# TurboTest.net
KiCad netlist of a schematic drawn in EAGLE
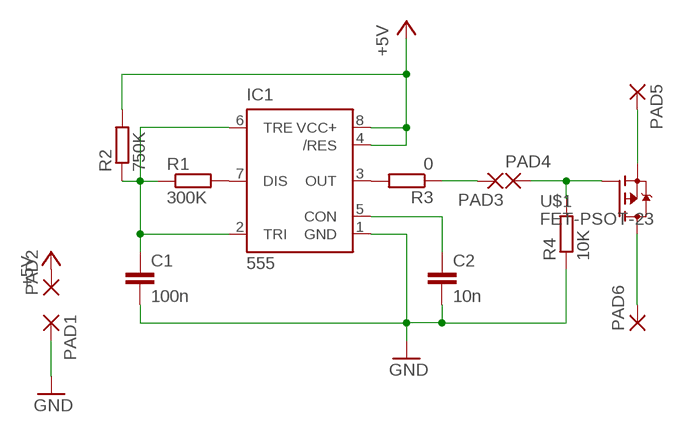
[diagram p0: schematic, sheet 1]

(export (version "E")
  (design (tool "Eeschema 10.0.6"))
  (components
    (comp (ref "C1")
      (value "100n")
      (footprint "eagle-import:CAP0805")
      (libsource (lib "eagle-import") (part "CAP_0805"))
    )
    (comp (ref "C2")
      (value "10n")
      (footprint "eagle-import:CAP0805")
      (libsource (lib "eagle-import") (part "CAP_0805"))
    )
    (comp (ref "IC1")
      (value "555")
      (footprint "eagle-import:SOIC-8")
      (libsource (lib "eagle-import") (part "IC-NE555SO8"))
    )
    (comp (ref "PAD1")
      (value "WIREPAD-SMD2")
      (footprint "eagle-import:PAD-1.27X2.54")
      (libsource (lib "eagle-import") (part "WIREPAD-SMD2"))
    )
    (comp (ref "PAD2")
      (value "WIREPAD-SMD2")
      (footprint "eagle-import:PAD-1.27X2.54")
      (libsource (lib "eagle-import") (part "WIREPAD-SMD2"))
    )
    (comp (ref "PAD3")
      (value "WIREPAD-SMD2")
      (footprint "eagle-import:PAD-1.27X2.54")
      (libsource (lib "eagle-import") (part "WIREPAD-SMD2"))
    )
    (comp (ref "PAD4")
      (value "WIREPAD-SMD2")
      (footprint "eagle-import:PAD-1.27X2.54")
      (libsource (lib "eagle-import") (part "WIREPAD-SMD2"))
    )
    (comp (ref "PAD5")
      (value "WIREPAD-SMD2")
      (footprint "eagle-import:PAD-1.27X2.54")
      (libsource (lib "eagle-import") (part "WIREPAD-SMD2"))
    )
    (comp (ref "PAD6")
      (value "WIREPAD-SMD2")
      (footprint "eagle-import:PAD-1.27X2.54")
      (libsource (lib "eagle-import") (part "WIREPAD-SMD2"))
    )
    (comp (ref "R1")
      (value "300K")
      (footprint "eagle-import:RESC2012X50")
      (libsource (lib "eagle-import") (part "R_R0805"))
    )
    (comp (ref "R2")
      (value "750K")
      (footprint "eagle-import:RESC2012X50")
      (libsource (lib "eagle-import") (part "R_R0805"))
    )
    (comp (ref "R3")
      (value "0")
      (footprint "eagle-import:RESC2012X50")
      (libsource (lib "eagle-import") (part "R_R0805"))
    )
    (comp (ref "R4")
      (value "10K")
      (footprint "eagle-import:RESC2012X50")
      (libsource (lib "eagle-import") (part "R_R0805"))
    )
    (comp (ref "U$1")
      (value "FET-PSOT-23")
      (footprint "eagle-import:SOT95P240X115-3")
      (libsource (lib "eagle-import") (part "FET-PSOT-23"))
    )
  )
  (nets
    (net (code "1") (name "+5V") (class "Default")
      (node (ref "IC1") (pin "4") (pinfunction "/RES_4") (pintype "input"))
      (node (ref "IC1") (pin "8") (pinfunction "VCC+_8") (pintype "power_in"))
      (node (ref "PAD2") (pin "P$1") (pinfunction "P_P$1") (pintype "passive"))
      (node (ref "R2") (pin "2") (pinfunction "2_2") (pintype "passive"))
    )
    (net (code "2") (name "GND") (class "Default")
      (node (ref "C1") (pin "2") (pinfunction "2_2") (pintype "passive"))
      (node (ref "C2") (pin "2") (pinfunction "2_2") (pintype "passive"))
      (node (ref "IC1") (pin "1") (pinfunction "GND_1") (pintype "power_in"))
      (node (ref "PAD1") (pin "P$1") (pinfunction "P_P$1") (pintype "passive"))
      (node (ref "R4") (pin "1") (pinfunction "1_1") (pintype "passive"))
    )
    (net (code "3") (name "Net-(IC1-CON)") (class "Default")
      (node (ref "C2") (pin "1") (pinfunction "1_1") (pintype "passive"))
      (node (ref "IC1") (pin "5") (pinfunction "CON_5") (pintype "input"))
    )
    (net (code "4") (name "Net-(IC1-DIS)") (class "Default")
      (node (ref "IC1") (pin "7") (pinfunction "DIS_7") (pintype "input"))
      (node (ref "R1") (pin "2") (pinfunction "2_2") (pintype "passive"))
    )
    (net (code "5") (name "Net-(IC1-OUT)") (class "Default")
      (node (ref "IC1") (pin "3") (pinfunction "OUT_3") (pintype "output"))
      (node (ref "R3") (pin "2") (pinfunction "2_2") (pintype "passive"))
    )
    (net (code "6") (name "Net-(IC1-TRE)") (class "Default")
      (node (ref "C1") (pin "1") (pinfunction "1_1") (pintype "passive"))
      (node (ref "IC1") (pin "2") (pinfunction "TRI_2") (pintype "input"))
      (node (ref "IC1") (pin "6") (pinfunction "TRE_6") (pintype "input"))
      (node (ref "R1") (pin "1") (pinfunction "1_1") (pintype "passive"))
      (node (ref "R2") (pin "1") (pinfunction "1_1") (pintype "passive"))
    )
    (net (code "7") (name "Net-(PAD3-P)") (class "Default")
      (node (ref "PAD3") (pin "P$1") (pinfunction "P_P$1") (pintype "passive"))
      (node (ref "R3") (pin "1") (pinfunction "1_1") (pintype "passive"))
    )
    (net (code "8") (name "Net-(PAD4-P)") (class "Default")
      (node (ref "PAD4") (pin "P$1") (pinfunction "P_P$1") (pintype "passive"))
      (node (ref "R4") (pin "2") (pinfunction "2_2") (pintype "passive"))
      (node (ref "U$1") (pin "1") (pinfunction "G_1") (pintype "passive"))
    )
    (net (code "9") (name "Net-(PAD5-P)") (class "Default")
      (node (ref "PAD5") (pin "P$1") (pinfunction "P_P$1") (pintype "passive"))
      (node (ref "U$1") (pin "2") (pinfunction "S_2") (pintype "passive"))
    )
    (net (code "10") (name "Net-(PAD6-P)") (class "Default")
      (node (ref "PAD6") (pin "P$1") (pinfunction "P_P$1") (pintype "passive"))
      (node (ref "U$1") (pin "3") (pinfunction "D_3") (pintype "passive"))
    )
  )
)
